# as14120_x31_fpga_power_conf.net
KiCad netlist of a schematic drawn in Altium Designer
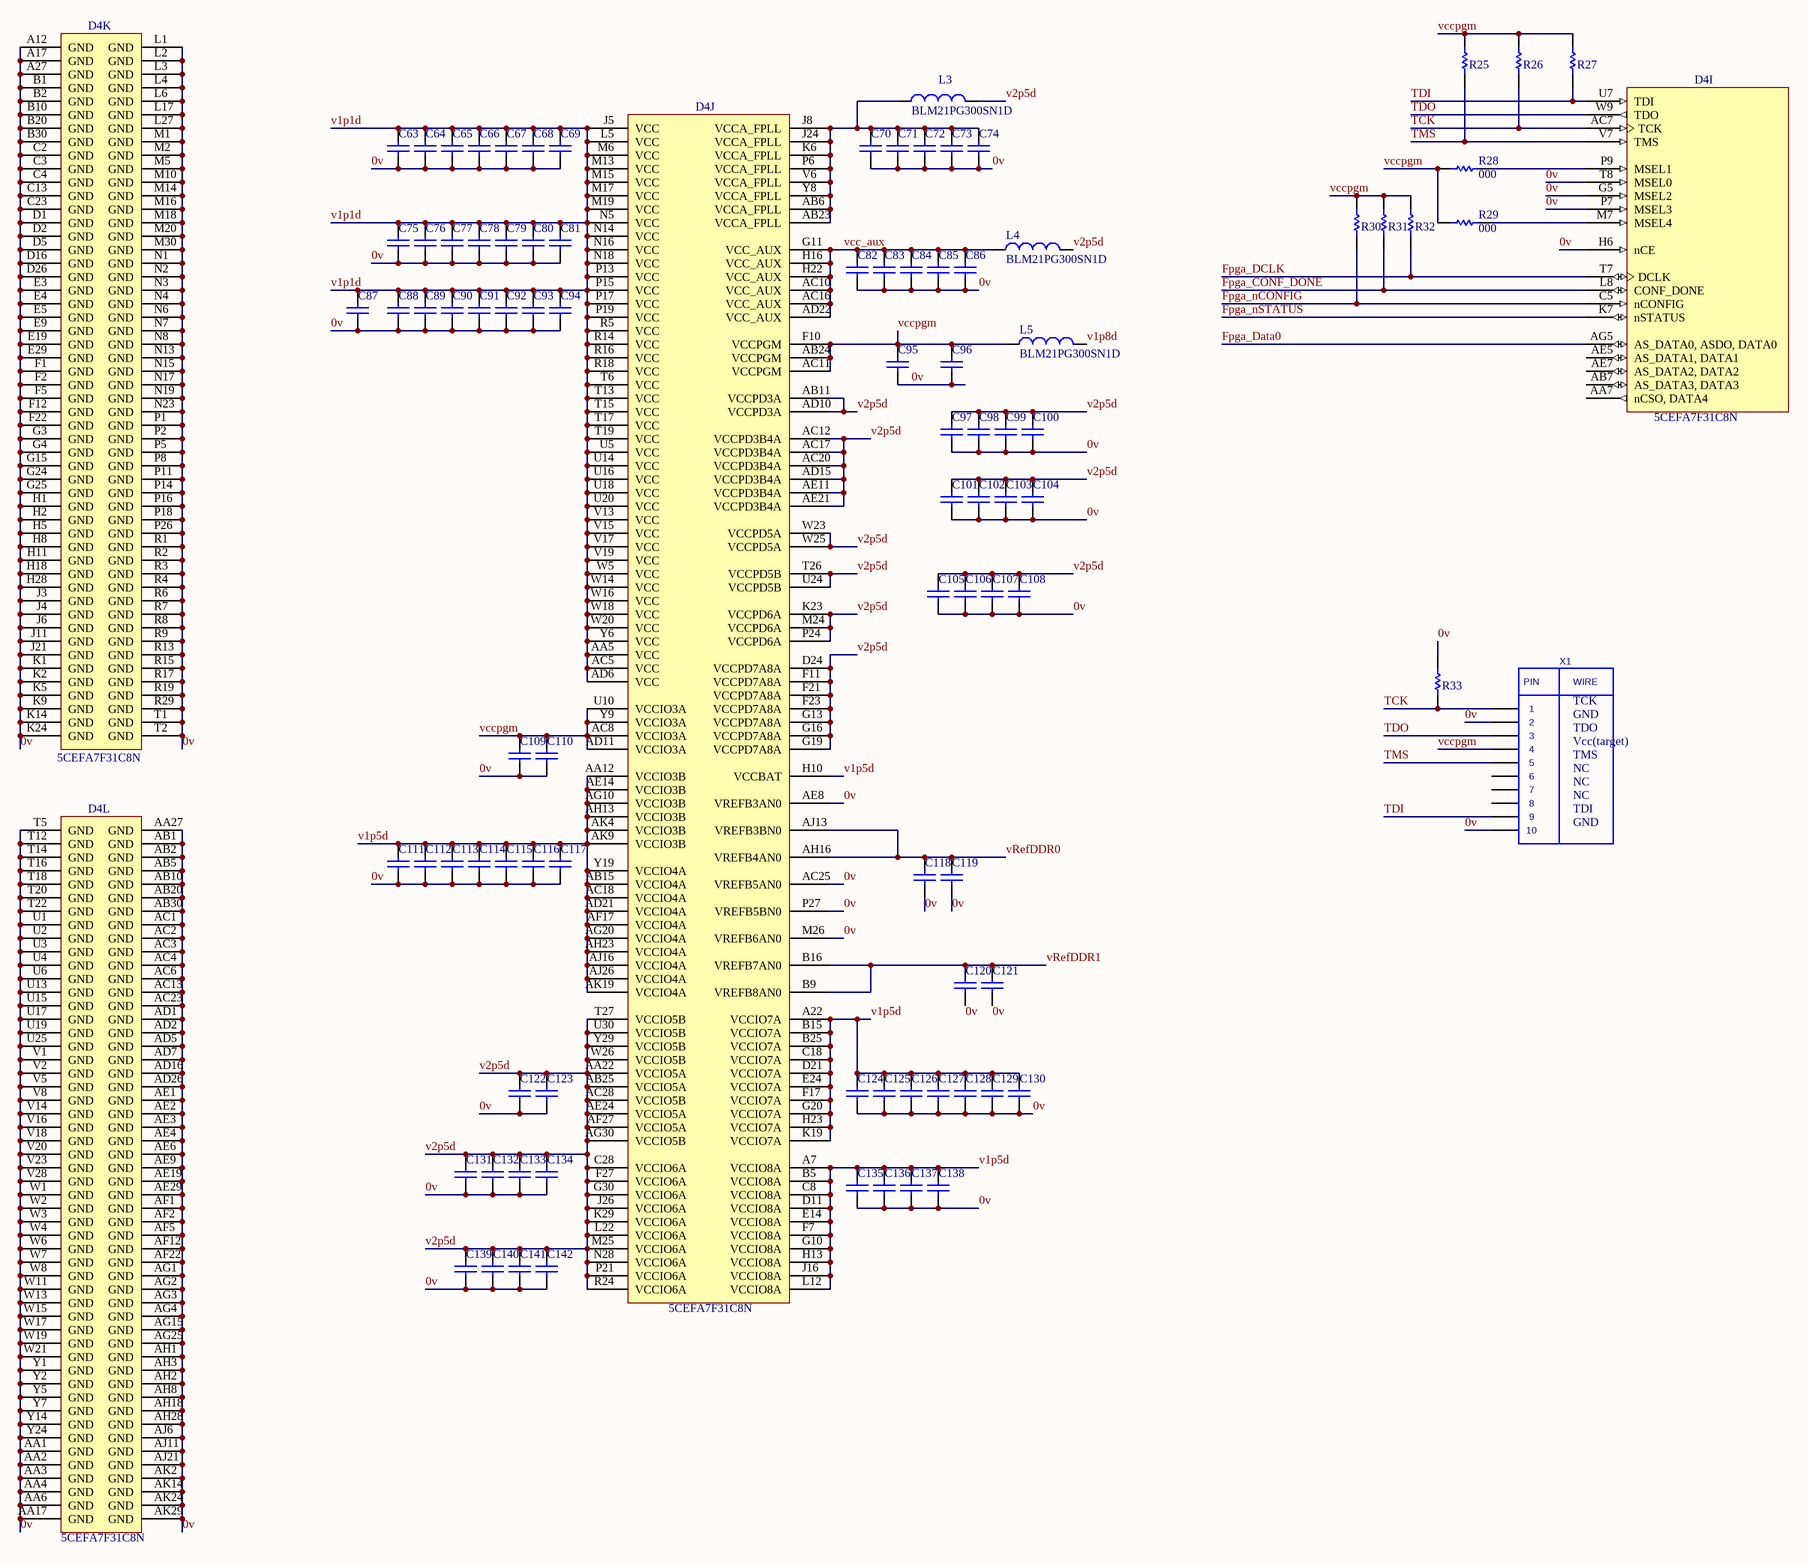
[diagram p0: as14120_x31_fpga_power_conf.SchDoc]

(export (version "E")
  (design (tool "Eeschema 10.0.6"))
  (components
    (comp (ref "C63")
      (value "CAP 1uF 10V 0402(1005)")
      (footprint "CAPC0402(1005)60_M")
      (description "CAP 1uF 10V ±20% 0402 (1005 Metric) Thickness 0.6mm SMD")
      (fields (field (name "TOLERANCE") "±20%"))
      (libsource (lib "as14120") (part "CAP_0402"))
    )
    (comp (ref "C64")
      (value "CAP 1uF 10V 0402(1005)")
      (footprint "CAPC0402(1005)60_M")
      (description "CAP 1uF 10V ±20% 0402 (1005 Metric) Thickness 0.6mm SMD")
      (fields (field (name "TOLERANCE") "±20%"))
      (libsource (lib "as14120") (part "CAP_0402"))
    )
    (comp (ref "C65")
      (value "CAP 1uF 10V 0402(1005)")
      (footprint "CAPC0402(1005)60_M")
      (description "CAP 1uF 10V ±20% 0402 (1005 Metric) Thickness 0.6mm SMD")
      (fields (field (name "TOLERANCE") "±20%"))
      (libsource (lib "as14120") (part "CAP_0402"))
    )
    (comp (ref "C66")
      (value "CAP 1uF 10V 0402(1005)")
      (footprint "CAPC0402(1005)60_M")
      (description "CAP 1uF 10V ±20% 0402 (1005 Metric) Thickness 0.6mm SMD")
      (fields (field (name "TOLERANCE") "±20%"))
      (libsource (lib "as14120") (part "CAP_0402"))
    )
    (comp (ref "C67")
      (value "CAP 1uF 10V 0402(1005)")
      (footprint "CAPC0402(1005)60_M")
      (description "CAP 1uF 10V ±20% 0402 (1005 Metric) Thickness 0.6mm SMD")
      (fields (field (name "TOLERANCE") "±20%"))
      (libsource (lib "as14120") (part "CAP_0402"))
    )
    (comp (ref "C68")
      (value "CAP 1uF 10V 0402(1005)")
      (footprint "CAPC0402(1005)60_M")
      (description "CAP 1uF 10V ±20% 0402 (1005 Metric) Thickness 0.6mm SMD")
      (fields (field (name "TOLERANCE") "±20%"))
      (libsource (lib "as14120") (part "CAP_0402"))
    )
    (comp (ref "C69")
      (value "CAP 1uF 10V 0402(1005)")
      (footprint "CAPC0402(1005)60_M")
      (description "CAP 1uF 10V ±20% 0402 (1005 Metric) Thickness 0.6mm SMD")
      (fields (field (name "TOLERANCE") "±20%"))
      (libsource (lib "as14120") (part "CAP_0402"))
    )
    (comp (ref "C70")
      (value "CAP 1uF 10V 0402(1005)")
      (footprint "CAPC0402(1005)60_M")
      (description "CAP 1uF 10V ±20% 0402 (1005 Metric) Thickness 0.6mm SMD")
      (fields (field (name "TOLERANCE") "±20%"))
      (libsource (lib "as14120") (part "CAP_0402"))
    )
    (comp (ref "C71")
      (value "CAP 1uF 10V 0402(1005)")
      (footprint "CAPC0402(1005)60_M")
      (description "CAP 1uF 10V ±20% 0402 (1005 Metric) Thickness 0.6mm SMD")
      (fields (field (name "TOLERANCE") "±20%"))
      (libsource (lib "as14120") (part "CAP_0402"))
    )
    (comp (ref "C72")
      (value "CAP 1uF 10V 0402(1005)")
      (footprint "CAPC0402(1005)60_M")
      (description "CAP 1uF 10V ±20% 0402 (1005 Metric) Thickness 0.6mm SMD")
      (fields (field (name "TOLERANCE") "±20%"))
      (libsource (lib "as14120") (part "CAP_0402"))
    )
    (comp (ref "C73")
      (value "CAP 1uF 10V 0402(1005)")
      (footprint "CAPC0402(1005)60_M")
      (description "CAP 1uF 10V ±20% 0402 (1005 Metric) Thickness 0.6mm SMD")
      (fields (field (name "TOLERANCE") "±20%"))
      (libsource (lib "as14120") (part "CAP_0402"))
    )
    (comp (ref "C74")
      (value "CAP 1uF 10V 0402(1005)")
      (footprint "CAPC0402(1005)60_M")
      (description "CAP 1uF 10V ±20% 0402 (1005 Metric) Thickness 0.6mm SMD")
      (fields (field (name "TOLERANCE") "±20%"))
      (libsource (lib "as14120") (part "CAP_0402"))
    )
    (comp (ref "C75")
      (value "CAP 1uF 10V 0402(1005)")
      (footprint "CAPC0402(1005)60_M")
      (description "CAP 1uF 10V ±20% 0402 (1005 Metric) Thickness 0.6mm SMD")
      (fields (field (name "TOLERANCE") "±20%"))
      (libsource (lib "as14120") (part "CAP_0402"))
    )
    (comp (ref "C76")
      (value "CAP 1uF 10V 0402(1005)")
      (footprint "CAPC0402(1005)60_M")
      (description "CAP 1uF 10V ±20% 0402 (1005 Metric) Thickness 0.6mm SMD")
      (fields (field (name "TOLERANCE") "±20%"))
      (libsource (lib "as14120") (part "CAP_0402"))
    )
    (comp (ref "C77")
      (value "CAP 1uF 10V 0402(1005)")
      (footprint "CAPC0402(1005)60_M")
      (description "CAP 1uF 10V ±20% 0402 (1005 Metric) Thickness 0.6mm SMD")
      (fields (field (name "TOLERANCE") "±20%"))
      (libsource (lib "as14120") (part "CAP_0402"))
    )
    (comp (ref "C78")
      (value "CAP 1uF 10V 0402(1005)")
      (footprint "CAPC0402(1005)60_M")
      (description "CAP 1uF 10V ±20% 0402 (1005 Metric) Thickness 0.6mm SMD")
      (fields (field (name "TOLERANCE") "±20%"))
      (libsource (lib "as14120") (part "CAP_0402"))
    )
    (comp (ref "C79")
      (value "CAP 1uF 10V 0402(1005)")
      (footprint "CAPC0402(1005)60_M")
      (description "CAP 1uF 10V ±20% 0402 (1005 Metric) Thickness 0.6mm SMD")
      (fields (field (name "TOLERANCE") "±20%"))
      (libsource (lib "as14120") (part "CAP_0402"))
    )
    (comp (ref "C80")
      (value "CAP 1uF 10V 0402(1005)")
      (footprint "CAPC0402(1005)60_M")
      (description "CAP 1uF 10V ±20% 0402 (1005 Metric) Thickness 0.6mm SMD")
      (fields (field (name "TOLERANCE") "±20%"))
      (libsource (lib "as14120") (part "CAP_0402"))
    )
    (comp (ref "C81")
      (value "CAP 1uF 10V 0402(1005)")
      (footprint "CAPC0402(1005)60_M")
      (description "CAP 1uF 10V ±20% 0402 (1005 Metric) Thickness 0.6mm SMD")
      (fields (field (name "TOLERANCE") "±20%"))
      (libsource (lib "as14120") (part "CAP_0402"))
    )
    (comp (ref "C82")
      (value "CAP 1uF 10V 0402(1005)")
      (footprint "CAPC0402(1005)60_M")
      (description "CAP 1uF 10V ±20% 0402 (1005 Metric) Thickness 0.6mm SMD")
      (fields (field (name "TOLERANCE") "±20%"))
      (libsource (lib "as14120") (part "CAP_0402"))
    )
    (comp (ref "C83")
      (value "CAP 1uF 10V 0402(1005)")
      (footprint "CAPC0402(1005)60_M")
      (description "CAP 1uF 10V ±20% 0402 (1005 Metric) Thickness 0.6mm SMD")
      (fields (field (name "TOLERANCE") "±20%"))
      (libsource (lib "as14120") (part "CAP_0402"))
    )
    (comp (ref "C84")
      (value "CAP 1uF 10V 0402(1005)")
      (footprint "CAPC0402(1005)60_M")
      (description "CAP 1uF 10V ±20% 0402 (1005 Metric) Thickness 0.6mm SMD")
      (fields (field (name "TOLERANCE") "±20%"))
      (libsource (lib "as14120") (part "CAP_0402"))
    )
    (comp (ref "C85")
      (value "CAP 1uF 10V 0402(1005)")
      (footprint "CAPC0402(1005)60_M")
      (description "CAP 1uF 10V ±20% 0402 (1005 Metric) Thickness 0.6mm SMD")
      (fields (field (name "TOLERANCE") "±20%"))
      (libsource (lib "as14120") (part "CAP_0402"))
    )
    (comp (ref "C86")
      (value "CAP 1uF 10V 0402(1005)")
      (footprint "CAPC0402(1005)60_M")
      (description "CAP 1uF 10V ±20% 0402 (1005 Metric) Thickness 0.6mm SMD")
      (fields (field (name "TOLERANCE") "±20%"))
      (libsource (lib "as14120") (part "CAP_0402"))
    )
    (comp (ref "C87")
      (value "CAP 1uF 10V 0402(1005)")
      (footprint "CAPC0402(1005)60_M")
      (description "CAP 1uF 10V ±20% 0402 (1005 Metric) Thickness 0.6mm SMD")
      (fields (field (name "TOLERANCE") "±20%"))
      (libsource (lib "as14120") (part "CAP_0402"))
    )
    (comp (ref "C88")
      (value "CAP 1uF 10V 0402(1005)")
      (footprint "CAPC0402(1005)60_M")
      (description "CAP 1uF 10V ±20% 0402 (1005 Metric) Thickness 0.6mm SMD")
      (fields (field (name "TOLERANCE") "±20%"))
      (libsource (lib "as14120") (part "CAP_0402"))
    )
    (comp (ref "C89")
      (value "CAP 1uF 10V 0402(1005)")
      (footprint "CAPC0402(1005)60_M")
      (description "CAP 1uF 10V ±20% 0402 (1005 Metric) Thickness 0.6mm SMD")
      (fields (field (name "TOLERANCE") "±20%"))
      (libsource (lib "as14120") (part "CAP_0402"))
    )
    (comp (ref "C90")
      (value "CAP 1uF 10V 0402(1005)")
      (footprint "CAPC0402(1005)60_M")
      (description "CAP 1uF 10V ±20% 0402 (1005 Metric) Thickness 0.6mm SMD")
      (fields (field (name "TOLERANCE") "±20%"))
      (libsource (lib "as14120") (part "CAP_0402"))
    )
    (comp (ref "C91")
      (value "CAP 1uF 10V 0402(1005)")
      (footprint "CAPC0402(1005)60_M")
      (description "CAP 1uF 10V ±20% 0402 (1005 Metric) Thickness 0.6mm SMD")
      (fields (field (name "TOLERANCE") "±20%"))
      (libsource (lib "as14120") (part "CAP_0402"))
    )
    (comp (ref "C92")
      (value "CAP 1uF 10V 0402(1005)")
      (footprint "CAPC0402(1005)60_M")
      (description "CAP 1uF 10V ±20% 0402 (1005 Metric) Thickness 0.6mm SMD")
      (fields (field (name "TOLERANCE") "±20%"))
      (libsource (lib "as14120") (part "CAP_0402"))
    )
    (comp (ref "C93")
      (value "CAP 1uF 10V 0402(1005)")
      (footprint "CAPC0402(1005)60_M")
      (description "CAP 1uF 10V ±20% 0402 (1005 Metric) Thickness 0.6mm SMD")
      (fields (field (name "TOLERANCE") "±20%"))
      (libsource (lib "as14120") (part "CAP_0402"))
    )
    (comp (ref "C94")
      (value "CAP 1uF 10V 0402(1005)")
      (footprint "CAPC0402(1005)60_M")
      (description "CAP 1uF 10V ±20% 0402 (1005 Metric) Thickness 0.6mm SMD")
      (fields (field (name "TOLERANCE") "±20%"))
      (libsource (lib "as14120") (part "CAP_0402"))
    )
    (comp (ref "C95")
      (value "CAP 1uF 10V 0402(1005)")
      (footprint "CAPC0402(1005)60_M")
      (description "CAP 1uF 10V ±20% 0402 (1005 Metric) Thickness 0.6mm SMD")
      (fields (field (name "TOLERANCE") "±20%"))
      (libsource (lib "as14120") (part "CAP_0402"))
    )
    (comp (ref "C96")
      (value "CAP 1uF 10V 0402(1005)")
      (footprint "CAPC0402(1005)60_M")
      (description "CAP 1uF 10V ±20% 0402 (1005 Metric) Thickness 0.6mm SMD")
      (fields (field (name "TOLERANCE") "±20%"))
      (libsource (lib "as14120") (part "CAP_0402"))
    )
    (comp (ref "C97")
      (value "CAP 1uF 10V 0402(1005)")
      (footprint "CAPC0402(1005)60_M")
      (description "CAP 1uF 10V ±20% 0402 (1005 Metric) Thickness 0.6mm SMD")
      (fields (field (name "TOLERANCE") "±20%"))
      (libsource (lib "as14120") (part "CAP_0402"))
    )
    (comp (ref "C98")
      (value "CAP 1uF 10V 0402(1005)")
      (footprint "CAPC0402(1005)60_M")
      (description "CAP 1uF 10V ±20% 0402 (1005 Metric) Thickness 0.6mm SMD")
      (fields (field (name "TOLERANCE") "±20%"))
      (libsource (lib "as14120") (part "CAP_0402"))
    )
    (comp (ref "C99")
      (value "CAP 1uF 10V 0402(1005)")
      (footprint "CAPC0402(1005)60_M")
      (description "CAP 1uF 10V ±20% 0402 (1005 Metric) Thickness 0.6mm SMD")
      (fields (field (name "TOLERANCE") "±20%"))
      (libsource (lib "as14120") (part "CAP_0402"))
    )
    (comp (ref "C100")
      (value "CAP 1uF 10V 0402(1005)")
      (footprint "CAPC0402(1005)60_M")
      (description "CAP 1uF 10V ±20% 0402 (1005 Metric) Thickness 0.6mm SMD")
      (fields (field (name "TOLERANCE") "±20%"))
      (libsource (lib "as14120") (part "CAP_0402"))
    )
    (comp (ref "C101")
      (value "CAP 1uF 10V 0402(1005)")
      (footprint "CAPC0402(1005)60_M")
      (description "CAP 1uF 10V ±20% 0402 (1005 Metric) Thickness 0.6mm SMD")
      (fields (field (name "TOLERANCE") "±20%"))
      (libsource (lib "as14120") (part "CAP_0402"))
    )
    (comp (ref "C102")
      (value "CAP 1uF 10V 0402(1005)")
      (footprint "CAPC0402(1005)60_M")
      (description "CAP 1uF 10V ±20% 0402 (1005 Metric) Thickness 0.6mm SMD")
      (fields (field (name "TOLERANCE") "±20%"))
      (libsource (lib "as14120") (part "CAP_0402"))
    )
    (comp (ref "C103")
      (value "CAP 1uF 10V 0402(1005)")
      (footprint "CAPC0402(1005)60_M")
      (description "CAP 1uF 10V ±20% 0402 (1005 Metric) Thickness 0.6mm SMD")
      (fields (field (name "TOLERANCE") "±20%"))
      (libsource (lib "as14120") (part "CAP_0402"))
    )
    (comp (ref "C104")
      (value "CAP 1uF 10V 0402(1005)")
      (footprint "CAPC0402(1005)60_M")
      (description "CAP 1uF 10V ±20% 0402 (1005 Metric) Thickness 0.6mm SMD")
      (fields (field (name "TOLERANCE") "±20%"))
      (libsource (lib "as14120") (part "CAP_0402"))
    )
    (comp (ref "C105")
      (value "CAP 1uF 10V 0402(1005)")
      (footprint "CAPC0402(1005)60_M")
      (description "CAP 1uF 10V ±20% 0402 (1005 Metric) Thickness 0.6mm SMD")
      (fields (field (name "TOLERANCE") "±20%"))
      (libsource (lib "as14120") (part "CAP_0402"))
    )
    (comp (ref "C106")
      (value "CAP 1uF 10V 0402(1005)")
      (footprint "CAPC0402(1005)60_M")
      (description "CAP 1uF 10V ±20% 0402 (1005 Metric) Thickness 0.6mm SMD")
      (fields (field (name "TOLERANCE") "±20%"))
      (libsource (lib "as14120") (part "CAP_0402"))
    )
    (comp (ref "C107")
      (value "CAP 1uF 10V 0402(1005)")
      (footprint "CAPC0402(1005)60_M")
      (description "CAP 1uF 10V ±20% 0402 (1005 Metric) Thickness 0.6mm SMD")
      (fields (field (name "TOLERANCE") "±20%"))
      (libsource (lib "as14120") (part "CAP_0402"))
    )
    (comp (ref "C108")
      (value "CAP 1uF 10V 0402(1005)")
      (footprint "CAPC0402(1005)60_M")
      (description "CAP 1uF 10V ±20% 0402 (1005 Metric) Thickness 0.6mm SMD")
      (fields (field (name "TOLERANCE") "±20%"))
      (libsource (lib "as14120") (part "CAP_0402"))
    )
    (comp (ref "C109")
      (value "CAP 1uF 10V 0402(1005)")
      (footprint "CAPC0402(1005)60_M")
      (description "CAP 1uF 10V ±20% 0402 (1005 Metric) Thickness 0.6mm SMD")
      (fields (field (name "TOLERANCE") "±20%"))
      (libsource (lib "as14120") (part "CAP_0402"))
    )
    (comp (ref "C110")
      (value "CAP 1uF 10V 0402(1005)")
      (footprint "CAPC0402(1005)60_M")
      (description "CAP 1uF 10V ±20% 0402 (1005 Metric) Thickness 0.6mm SMD")
      (fields (field (name "TOLERANCE") "±20%"))
      (libsource (lib "as14120") (part "CAP_0402"))
    )
    (comp (ref "C111")
      (value "CAP 1uF 10V 0402(1005)")
      (footprint "CAPC0402(1005)60_M")
      (description "CAP 1uF 10V ±20% 0402 (1005 Metric) Thickness 0.6mm SMD")
      (fields (field (name "TOLERANCE") "±20%"))
      (libsource (lib "as14120") (part "CAP_0402"))
    )
    (comp (ref "C112")
      (value "CAP 1uF 10V 0402(1005)")
      (footprint "CAPC0402(1005)60_M")
      (description "CAP 1uF 10V ±20% 0402 (1005 Metric) Thickness 0.6mm SMD")
      (fields (field (name "TOLERANCE") "±20%"))
      (libsource (lib "as14120") (part "CAP_0402"))
    )
    (comp (ref "C113")
      (value "CAP 1uF 10V 0402(1005)")
      (footprint "CAPC0402(1005)60_M")
      (description "CAP 1uF 10V ±20% 0402 (1005 Metric) Thickness 0.6mm SMD")
      (fields (field (name "TOLERANCE") "±20%"))
      (libsource (lib "as14120") (part "CAP_0402"))
    )
    (comp (ref "C114")
      (value "CAP 1uF 10V 0402(1005)")
      (footprint "CAPC0402(1005)60_M")
      (description "CAP 1uF 10V ±20% 0402 (1005 Metric) Thickness 0.6mm SMD")
      (fields (field (name "TOLERANCE") "±20%"))
      (libsource (lib "as14120") (part "CAP_0402"))
    )
    (comp (ref "C115")
      (value "CAP 1uF 10V 0402(1005)")
      (footprint "CAPC0402(1005)60_M")
      (description "CAP 1uF 10V ±20% 0402 (1005 Metric) Thickness 0.6mm SMD")
      (fields (field (name "TOLERANCE") "±20%"))
      (libsource (lib "as14120") (part "CAP_0402"))
    )
    (comp (ref "C116")
      (value "CAP 1uF 10V 0402(1005)")
      (footprint "CAPC0402(1005)60_M")
      (description "CAP 1uF 10V ±20% 0402 (1005 Metric) Thickness 0.6mm SMD")
      (fields (field (name "TOLERANCE") "±20%"))
      (libsource (lib "as14120") (part "CAP_0402"))
    )
    (comp (ref "C117")
      (value "CAP 1uF 10V 0402(1005)")
      (footprint "CAPC0402(1005)60_M")
      (description "CAP 1uF 10V ±20% 0402 (1005 Metric) Thickness 0.6mm SMD")
      (fields (field (name "TOLERANCE") "±20%"))
      (libsource (lib "as14120") (part "CAP_0402"))
    )
    (comp (ref "C118")
      (value "CAP 1uF 10V 0402(1005)")
      (footprint "CAPC0402(1005)60_M")
      (description "CAP 1uF 10V ±20% 0402 (1005 Metric) Thickness 0.6mm SMD")
      (fields (field (name "TOLERANCE") "±20%"))
      (libsource (lib "as14120") (part "CAP_0402"))
    )
    (comp (ref "C119")
      (value "CAP 1uF 10V 0402(1005)")
      (footprint "CAPC0402(1005)60_M")
      (description "CAP 1uF 10V ±20% 0402 (1005 Metric) Thickness 0.6mm SMD")
      (fields (field (name "TOLERANCE") "±20%"))
      (libsource (lib "as14120") (part "CAP_0402"))
    )
    (comp (ref "C120")
      (value "CAP 1uF 10V 0402(1005)")
      (footprint "CAPC0402(1005)60_M")
      (description "CAP 1uF 10V ±20% 0402 (1005 Metric) Thickness 0.6mm SMD")
      (fields (field (name "TOLERANCE") "±20%"))
      (libsource (lib "as14120") (part "CAP_0402"))
    )
    (comp (ref "C121")
      (value "CAP 1uF 10V 0402(1005)")
      (footprint "CAPC0402(1005)60_M")
      (description "CAP 1uF 10V ±20% 0402 (1005 Metric) Thickness 0.6mm SMD")
      (fields (field (name "TOLERANCE") "±20%"))
      (libsource (lib "as14120") (part "CAP_0402"))
    )
    (comp (ref "C122")
      (value "CAP 1uF 10V 0402(1005)")
      (footprint "CAPC0402(1005)60_M")
      (description "CAP 1uF 10V ±20% 0402 (1005 Metric) Thickness 0.6mm SMD")
      (fields (field (name "TOLERANCE") "±20%"))
      (libsource (lib "as14120") (part "CAP_0402"))
    )
    (comp (ref "C123")
      (value "CAP 1uF 10V 0402(1005)")
      (footprint "CAPC0402(1005)60_M")
      (description "CAP 1uF 10V ±20% 0402 (1005 Metric) Thickness 0.6mm SMD")
      (fields (field (name "TOLERANCE") "±20%"))
      (libsource (lib "as14120") (part "CAP_0402"))
    )
    (comp (ref "C124")
      (value "CAP 1uF 10V 0402(1005)")
      (footprint "CAPC0402(1005)60_M")
      (description "CAP 1uF 10V ±20% 0402 (1005 Metric) Thickness 0.6mm SMD")
      (fields (field (name "TOLERANCE") "±20%"))
      (libsource (lib "as14120") (part "CAP_0402"))
    )
    (comp (ref "C125")
      (value "CAP 1uF 10V 0402(1005)")
      (footprint "CAPC0402(1005)60_M")
      (description "CAP 1uF 10V ±20% 0402 (1005 Metric) Thickness 0.6mm SMD")
      (fields (field (name "TOLERANCE") "±20%"))
      (libsource (lib "as14120") (part "CAP_0402"))
    )
    (comp (ref "C126")
      (value "CAP 1uF 10V 0402(1005)")
      (footprint "CAPC0402(1005)60_M")
      (description "CAP 1uF 10V ±20% 0402 (1005 Metric) Thickness 0.6mm SMD")
      (fields (field (name "TOLERANCE") "±20%"))
      (libsource (lib "as14120") (part "CAP_0402"))
    )
    (comp (ref "C127")
      (value "CAP 1uF 10V 0402(1005)")
      (footprint "CAPC0402(1005)60_M")
      (description "CAP 1uF 10V ±20% 0402 (1005 Metric) Thickness 0.6mm SMD")
      (fields (field (name "TOLERANCE") "±20%"))
      (libsource (lib "as14120") (part "CAP_0402"))
    )
    (comp (ref "C128")
      (value "CAP 1uF 10V 0402(1005)")
      (footprint "CAPC0402(1005)60_M")
      (description "CAP 1uF 10V ±20% 0402 (1005 Metric) Thickness 0.6mm SMD")
      (fields (field (name "TOLERANCE") "±20%"))
      (libsource (lib "as14120") (part "CAP_0402"))
    )
    (comp (ref "C129")
      (value "CAP 1uF 10V 0402(1005)")
      (footprint "CAPC0402(1005)60_M")
      (description "CAP 1uF 10V ±20% 0402 (1005 Metric) Thickness 0.6mm SMD")
      (fields (field (name "TOLERANCE") "±20%"))
      (libsource (lib "as14120") (part "CAP_0402"))
    )
    (comp (ref "C130")
      (value "CAP 1uF 10V 0402(1005)")
      (footprint "CAPC0402(1005)60_M")
      (description "CAP 1uF 10V ±20% 0402 (1005 Metric) Thickness 0.6mm SMD")
      (fields (field (name "TOLERANCE") "±20%"))
      (libsource (lib "as14120") (part "CAP_0402"))
    )
    (comp (ref "C131")
      (value "CAP 1uF 10V 0402(1005)")
      (footprint "CAPC0402(1005)60_M")
      (description "CAP 1uF 10V ±20% 0402 (1005 Metric) Thickness 0.6mm SMD")
      (fields (field (name "TOLERANCE") "±20%"))
      (libsource (lib "as14120") (part "CAP_0402"))
    )
    (comp (ref "C132")
      (value "CAP 1uF 10V 0402(1005)")
      (footprint "CAPC0402(1005)60_M")
      (description "CAP 1uF 10V ±20% 0402 (1005 Metric) Thickness 0.6mm SMD")
      (fields (field (name "TOLERANCE") "±20%"))
      (libsource (lib "as14120") (part "CAP_0402"))
    )
    (comp (ref "C133")
      (value "CAP 1uF 10V 0402(1005)")
      (footprint "CAPC0402(1005)60_M")
      (description "CAP 1uF 10V ±20% 0402 (1005 Metric) Thickness 0.6mm SMD")
      (fields (field (name "TOLERANCE") "±20%"))
      (libsource (lib "as14120") (part "CAP_0402"))
    )
    (comp (ref "C134")
      (value "CAP 1uF 10V 0402(1005)")
      (footprint "CAPC0402(1005)60_M")
      (description "CAP 1uF 10V ±20% 0402 (1005 Metric) Thickness 0.6mm SMD")
      (fields (field (name "TOLERANCE") "±20%"))
      (libsource (lib "as14120") (part "CAP_0402"))
    )
    (comp (ref "C135")
      (value "CAP 1uF 10V 0402(1005)")
      (footprint "CAPC0402(1005)60_M")
      (description "CAP 1uF 10V ±20% 0402 (1005 Metric) Thickness 0.6mm SMD")
      (fields (field (name "TOLERANCE") "±20%"))
      (libsource (lib "as14120") (part "CAP_0402"))
    )
    (comp (ref "C136")
      (value "CAP 1uF 10V 0402(1005)")
      (footprint "CAPC0402(1005)60_M")
      (description "CAP 1uF 10V ±20% 0402 (1005 Metric) Thickness 0.6mm SMD")
      (fields (field (name "TOLERANCE") "±20%"))
      (libsource (lib "as14120") (part "CAP_0402"))
    )
    (comp (ref "C137")
      (value "CAP 1uF 10V 0402(1005)")
      (footprint "CAPC0402(1005)60_M")
      (description "CAP 1uF 10V ±20% 0402 (1005 Metric) Thickness 0.6mm SMD")
      (fields (field (name "TOLERANCE") "±20%"))
      (libsource (lib "as14120") (part "CAP_0402"))
    )
    (comp (ref "C138")
      (value "CAP 1uF 10V 0402(1005)")
      (footprint "CAPC0402(1005)60_M")
      (description "CAP 1uF 10V ±20% 0402 (1005 Metric) Thickness 0.6mm SMD")
      (fields (field (name "TOLERANCE") "±20%"))
      (libsource (lib "as14120") (part "CAP_0402"))
    )
    (comp (ref "C139")
      (value "CAP 1uF 10V 0402(1005)")
      (footprint "CAPC0402(1005)60_M")
      (description "CAP 1uF 10V ±20% 0402 (1005 Metric) Thickness 0.6mm SMD")
      (fields (field (name "TOLERANCE") "±20%"))
      (libsource (lib "as14120") (part "CAP_0402"))
    )
    (comp (ref "C140")
      (value "CAP 1uF 10V 0402(1005)")
      (footprint "CAPC0402(1005)60_M")
      (description "CAP 1uF 10V ±20% 0402 (1005 Metric) Thickness 0.6mm SMD")
      (fields (field (name "TOLERANCE") "±20%"))
      (libsource (lib "as14120") (part "CAP_0402"))
    )
    (comp (ref "C141")
      (value "CAP 1uF 10V 0402(1005)")
      (footprint "CAPC0402(1005)60_M")
      (description "CAP 1uF 10V ±20% 0402 (1005 Metric) Thickness 0.6mm SMD")
      (fields (field (name "TOLERANCE") "±20%"))
      (libsource (lib "as14120") (part "CAP_0402"))
    )
    (comp (ref "C142")
      (value "CAP 1uF 10V 0402(1005)")
      (footprint "CAPC0402(1005)60_M")
      (description "CAP 1uF 10V ±20% 0402 (1005 Metric) Thickness 0.6mm SMD")
      (fields (field (name "TOLERANCE") "±20%"))
      (libsource (lib "as14120") (part "CAP_0402"))
    )
    (comp (ref "D4")
      (value "5CEFA7F31C8N")
      (footprint "ALTR-896-FBGA-2000A")
      (fields (field (name "MANUFACTURER") "Altera"))
      (libsource (lib "Altera Cyclone V E") (part "5CEFA7F31C8N"))
    )
    (comp (ref "L3")
      (value "BLM21PG300SN1D")
      (footprint "CAPC0805(2012)100_N")
      (libsource (lib "as14120") (part "Ferrite_beat"))
    )
    (comp (ref "L4")
      (value "BLM21PG300SN1D")
      (footprint "CAPC0805(2012)100_N")
      (libsource (lib "as14120") (part "Ferrite_beat"))
    )
    (comp (ref "L5")
      (value "BLM21PG300SN1D")
      (footprint "CAPC0805(2012)100_N")
      (libsource (lib "as14120") (part "Ferrite_beat"))
    )
    (comp (ref "R25")
      (value "1K 5% 0603(1608)")
      (footprint "RESC0603(1608)_L")
      (description "1K 0.1W 5% 0603 (1608 Metric)  SMD")
      (fields (field (name "TOLERANCE") "5 %") (field (name "POWER") "0.1 W"))
      (libsource (lib "as14120") (part "RES_0603"))
    )
    (comp (ref "R26")
      (value "1K 5% 0603(1608)")
      (footprint "RESC0603(1608)_L")
      (description "1K 0.1W 5% 0603 (1608 Metric)  SMD")
      (fields (field (name "TOLERANCE") "5 %") (field (name "POWER") "0.1 W"))
      (libsource (lib "as14120") (part "RES_0603"))
    )
    (comp (ref "R27")
      (value "1K 5% 0603(1608)")
      (footprint "RESC0603(1608)_L")
      (description "1K 0.1W 5% 0603 (1608 Metric)  SMD")
      (fields (field (name "TOLERANCE") "5 %") (field (name "POWER") "0.1 W"))
      (libsource (lib "as14120") (part "RES_0603"))
    )
    (comp (ref "R28")
      (value "000")
      (footprint "RESC0603(1608)_L")
      (description "1K 0.1W 5% 0603 (1608 Metric)  SMD")
      (fields (field (name "TOLERANCE") "5 %") (field (name "POWER") "0.1 W"))
      (libsource (lib "as14120") (part "RES_0603"))
    )
    (comp (ref "R29")
      (value "000")
      (footprint "RESC0603(1608)_L")
      (description "1K 0.1W 5% 0603 (1608 Metric)  SMD")
      (fields (field (name "TOLERANCE") "5 %") (field (name "POWER") "0.1 W"))
      (libsource (lib "as14120") (part "RES_0603"))
    )
    (comp (ref "R30")
      (value "1K 5% 0603(1608)")
      (footprint "RESC0603(1608)_L")
      (description "1K 0.1W 5% 0603 (1608 Metric)  SMD")
      (fields (field (name "TOLERANCE") "5 %") (field (name "POWER") "0.1 W"))
      (libsource (lib "as14120") (part "RES_0603"))
    )
    (comp (ref "R31")
      (value "1K 5% 0603(1608)")
      (footprint "RESC0603(1608)_L")
      (description "1K 0.1W 5% 0603 (1608 Metric)  SMD")
      (fields (field (name "TOLERANCE") "5 %") (field (name "POWER") "0.1 W"))
      (libsource (lib "as14120") (part "RES_0603"))
    )
    (comp (ref "R32")
      (value "1K 5% 0603(1608)")
      (footprint "RESC0603(1608)_L")
      (description "1K 0.1W 5% 0603 (1608 Metric)  SMD")
      (fields (field (name "TOLERANCE") "5 %") (field (name "POWER") "0.1 W"))
      (libsource (lib "as14120") (part "RES_0603"))
    )
    (comp (ref "R33")
      (value "1K 5% 0603(1608)")
      (footprint "RESC0603(1608)_L")
      (description "1K 0.1W 5% 0603 (1608 Metric)  SMD")
      (fields (field (name "TOLERANCE") "5 %") (field (name "POWER") "0.1 W"))
      (libsource (lib "as14120") (part "RES_0603"))
    )
    (comp (ref "X1") (value "IDC10") (footprint "IDC10M") (libsource (lib "alexsb") (part "IDC10")))
  )
  (nets
    (net (code "1") (name "/0v") (class "Default")
      (node (ref "C100") (pin "1") (pinfunction "1_1") (pintype "passive"))
      (node (ref "C101") (pin "1") (pinfunction "1_1") (pintype "passive"))
      (node (ref "C102") (pin "1") (pinfunction "1_1") (pintype "passive"))
      (node (ref "C103") (pin "1") (pinfunction "1_1") (pintype "passive"))
      (node (ref "C104") (pin "1") (pinfunction "1_1") (pintype "passive"))
      (node (ref "C105") (pin "1") (pinfunction "1_1") (pintype "passive"))
      (node (ref "C106") (pin "1") (pinfunction "1_1") (pintype "passive"))
      (node (ref "C107") (pin "1") (pinfunction "1_1") (pintype "passive"))
      (node (ref "C108") (pin "1") (pinfunction "1_1") (pintype "passive"))
      (node (ref "C109") (pin "1") (pinfunction "1_1") (pintype "passive"))
      (node (ref "C110") (pin "1") (pinfunction "1_1") (pintype "passive"))
      (node (ref "C111") (pin "1") (pinfunction "1_1") (pintype "passive"))
      (node (ref "C112") (pin "1") (pinfunction "1_1") (pintype "passive"))
      (node (ref "C113") (pin "1") (pinfunction "1_1") (pintype "passive"))
      (node (ref "C114") (pin "1") (pinfunction "1_1") (pintype "passive"))
      (node (ref "C115") (pin "1") (pinfunction "1_1") (pintype "passive"))
      (node (ref "C116") (pin "1") (pinfunction "1_1") (pintype "passive"))
      (node (ref "C117") (pin "1") (pinfunction "1_1") (pintype "passive"))
      (node (ref "C118") (pin "1") (pinfunction "1_1") (pintype "passive"))
      (node (ref "C119") (pin "1") (pinfunction "1_1") (pintype "passive"))
      (node (ref "C122") (pin "1") (pinfunction "1_1") (pintype "passive"))
      (node (ref "C123") (pin "1") (pinfunction "1_1") (pintype "passive"))
      (node (ref "C124") (pin "1") (pinfunction "1_1") (pintype "passive"))
      (node (ref "C125") (pin "1") (pinfunction "1_1") (pintype "passive"))
      (node (ref "C126") (pin "1") (pinfunction "1_1") (pintype "passive"))
      (node (ref "C127") (pin "1") (pinfunction "1_1") (pintype "passive"))
      (node (ref "C128") (pin "1") (pinfunction "1_1") (pintype "passive"))
      (node (ref "C129") (pin "1") (pinfunction "1_1") (pintype "passive"))
      (node (ref "C130") (pin "1") (pinfunction "1_1") (pintype "passive"))
      (node (ref "C131") (pin "1") (pinfunction "1_1") (pintype "passive"))
      (node (ref "C132") (pin "1") (pinfunction "1_1") (pintype "passive"))
      (node (ref "C133") (pin "1") (pinfunction "1_1") (pintype "passive"))
      (node (ref "C134") (pin "1") (pinfunction "1_1") (pintype "passive"))
      (node (ref "C135") (pin "1") (pinfunction "1_1") (pintype "passive"))
      (node (ref "C136") (pin "1") (pinfunction "1_1") (pintype "passive"))
      (node (ref "C137") (pin "1") (pinfunction "1_1") (pintype "passive"))
      (node (ref "C138") (pin "1") (pinfunction "1_1") (pintype "passive"))
      (node (ref "C139") (pin "1") (pinfunction "1_1") (pintype "passive"))
      (node (ref "C140") (pin "1") (pinfunction "1_1") (pintype "passive"))
      (node (ref "C141") (pin "1") (pinfunction "1_1") (pintype "passive"))
      (node (ref "C142") (pin "1") (pinfunction "1_1") (pintype "passive"))
      (node (ref "C63") (pin "1") (pinfunction "1_1") (pintype "passive"))
      (node (ref "C64") (pin "1") (pinfunction "1_1") (pintype "passive"))
      (node (ref "C65") (pin "1") (pinfunction "1_1") (pintype "passive"))
      (node (ref "C66") (pin "1") (pinfunction "1_1") (pintype "passive"))
      (node (ref "C67") (pin "1") (pinfunction "1_1") (pintype "passive"))
      (node (ref "C68") (pin "1") (pinfunction "1_1") (pintype "passive"))
      (node (ref "C69") (pin "1") (pinfunction "1_1") (pintype "passive"))
      (node (ref "C70") (pin "1") (pinfunction "1_1") (pintype "passive"))
      (node (ref "C71") (pin "1") (pinfunction "1_1") (pintype "passive"))
      (node (ref "C72") (pin "1") (pinfunction "1_1") (pintype "passive"))
      (node (ref "C73") (pin "1") (pinfunction "1_1") (pintype "passive"))
      (node (ref "C74") (pin "1") (pinfunction "1_1") (pintype "passive"))
      (node (ref "C75") (pin "1") (pinfunction "1_1") (pintype "passive"))
      (node (ref "C76") (pin "1") (pinfunction "1_1") (pintype "passive"))
      (node (ref "C77") (pin "1") (pinfunction "1_1") (pintype "passive"))
      (node (ref "C78") (pin "1") (pinfunction "1_1") (pintype "passive"))
      (node (ref "C79") (pin "1") (pinfunction "1_1") (pintype "passive"))
      (node (ref "C80") (pin "1") (pinfunction "1_1") (pintype "passive"))
      (node (ref "C81") (pin "1") (pinfunction "1_1") (pintype "passive"))
      (node (ref "C82") (pin "1") (pinfunction "1_1") (pintype "passive"))
      (node (ref "C83") (pin "1") (pinfunction "1_1") (pintype "passive"))
      (node (ref "C84") (pin "1") (pinfunction "1_1") (pintype "passive"))
      (node (ref "C85") (pin "1") (pinfunction "1_1") (pintype "passive"))
      (node (ref "C86") (pin "1") (pinfunction "1_1") (pintype "passive"))
      (node (ref "C87") (pin "1") (pinfunction "1_1") (pintype "passive"))
      (node (ref "C88") (pin "1") (pinfunction "1_1") (pintype "passive"))
      (node (ref "C89") (pin "1") (pinfunction "1_1") (pintype "passive"))
      (node (ref "C90") (pin "1") (pinfunction "1_1") (pintype "passive"))
      (node (ref "C91") (pin "1") (pinfunction "1_1") (pintype "passive"))
      (node (ref "C92") (pin "1") (pinfunction "1_1") (pintype "passive"))
      (node (ref "C93") (pin "1") (pinfunction "1_1") (pintype "passive"))
      (node (ref "C94") (pin "1") (pinfunction "1_1") (pintype "passive"))
      (node (ref "C95") (pin "1") (pinfunction "1_1") (pintype "passive"))
      (node (ref "C96") (pin "1") (pinfunction "1_1") (pintype "passive"))
      (node (ref "C97") (pin "1") (pinfunction "1_1") (pintype "passive"))
      (node (ref "C98") (pin "1") (pinfunction "1_1") (pintype "passive"))
      (node (ref "C99") (pin "1") (pinfunction "1_1") (pintype "passive"))
      (node (ref "D4") (pin "A12") (pinfunction "GND_A12") (pintype "power_in"))
      (node (ref "D4") (pin "A17") (pinfunction "GND_A17") (pintype "power_in"))
      (node (ref "D4") (pin "A27") (pinfunction "GND_A27") (pintype "power_in"))
      (node (ref "D4") (pin "AA1") (pinfunction "GND_AA1") (pintype "power_in"))
      (node (ref "D4") (pin "AA17") (pinfunction "GND_AA17") (pintype "power_in"))
      (node (ref "D4") (pin "AA2") (pinfunction "GND_AA2") (pintype "power_in"))
      (node (ref "D4") (pin "AA27") (pinfunction "GND_AA27") (pintype "power_in"))
      (node (ref "D4") (pin "AA3") (pinfunction "GND_AA3") (pintype "power_in"))
      (node (ref "D4") (pin "AA4") (pinfunction "GND_AA4") (pintype "power_in"))
      (node (ref "D4") (pin "AA6") (pinfunction "GND_AA6") (pintype "power_in"))
      (node (ref "D4") (pin "AB1") (pinfunction "GND_AB1") (pintype "power_in"))
      (node (ref "D4") (pin "AB10") (pinfunction "GND_AB10") (pintype "power_in"))
      (node (ref "D4") (pin "AB2") (pinfunction "GND_AB2") (pintype "power_in"))
      (node (ref "D4") (pin "AB20") (pinfunction "GND_AB20") (pintype "power_in"))
      (node (ref "D4") (pin "AB30") (pinfunction "GND_AB30") (pintype "power_in"))
      (node (ref "D4") (pin "AB5") (pinfunction "GND_AB5") (pintype "power_in"))
      (node (ref "D4") (pin "AC1") (pinfunction "GND_AC1") (pintype "power_in"))
      (node (ref "D4") (pin "AC13") (pinfunction "GND_AC13") (pintype "power_in"))
      (node (ref "D4") (pin "AC2") (pinfunction "GND_AC2") (pintype "power_in"))
      (node (ref "D4") (pin "AC23") (pinfunction "GND_AC23") (pintype "power_in"))
      (node (ref "D4") (pin "AC25") (pinfunction "VREFB5AN0_AC25") (pintype "power_in"))
      (node (ref "D4") (pin "AC3") (pinfunction "GND_AC3") (pintype "power_in"))
      (node (ref "D4") (pin "AC4") (pinfunction "GND_AC4") (pintype "power_in"))
      (node (ref "D4") (pin "AC6") (pinfunction "GND_AC6") (pintype "power_in"))
      (node (ref "D4") (pin "AD1") (pinfunction "GND_AD1") (pintype "power_in"))
      (node (ref "D4") (pin "AD16") (pinfunction "GND_AD16") (pintype "power_in"))
      (node (ref "D4") (pin "AD2") (pinfunction "GND_AD2") (pintype "power_in"))
      (node (ref "D4") (pin "AD26") (pinfunction "GND_AD26") (pintype "power_in"))
      (node (ref "D4") (pin "AD5") (pinfunction "GND_AD5") (pintype "power_in"))
      (node (ref "D4") (pin "AD7") (pinfunction "GND_AD7") (pintype "power_in"))
      (node (ref "D4") (pin "AE1") (pinfunction "GND_AE1") (pintype "power_in"))
      (node (ref "D4") (pin "AE19") (pinfunction "GND_AE19") (pintype "power_in"))
      (node (ref "D4") (pin "AE2") (pinfunction "GND_AE2") (pintype "power_in"))
      (node (ref "D4") (pin "AE29") (pinfunction "GND_AE29") (pintype "power_in"))
      (node (ref "D4") (pin "AE3") (pinfunction "GND_AE3") (pintype "power_in"))
      (node (ref "D4") (pin "AE4") (pinfunction "GND_AE4") (pintype "power_in"))
      (node (ref "D4") (pin "AE6") (pinfunction "GND_AE6") (pintype "power_in"))
      (node (ref "D4") (pin "AE8") (pinfunction "VREFB3AN0_AE8") (pintype "power_in"))
      (node (ref "D4") (pin "AE9") (pinfunction "GND_AE9") (pintype "power_in"))
      (node (ref "D4") (pin "AF1") (pinfunction "GND_AF1") (pintype "power_in"))
      (node (ref "D4") (pin "AF12") (pinfunction "GND_AF12") (pintype "power_in"))
      (node (ref "D4") (pin "AF2") (pinfunction "GND_AF2") (pintype "power_in"))
      (node (ref "D4") (pin "AF22") (pinfunction "GND_AF22") (pintype "power_in"))
      (node (ref "D4") (pin "AF5") (pinfunction "GND_AF5") (pintype "power_in"))
      (node (ref "D4") (pin "AG1") (pinfunction "GND_AG1") (pintype "power_in"))
      (node (ref "D4") (pin "AG15") (pinfunction "GND_AG15") (pintype "power_in"))
      (node (ref "D4") (pin "AG2") (pinfunction "GND_AG2") (pintype "power_in"))
      (node (ref "D4") (pin "AG25") (pinfunction "GND_AG25") (pintype "power_in"))
      (node (ref "D4") (pin "AG3") (pinfunction "GND_AG3") (pintype "power_in"))
      (node (ref "D4") (pin "AG4") (pinfunction "GND_AG4") (pintype "power_in"))
      (node (ref "D4") (pin "AH1") (pinfunction "GND_AH1") (pintype "power_in"))
      (node (ref "D4") (pin "AH18") (pinfunction "GND_AH18") (pintype "power_in"))
      (node (ref "D4") (pin "AH2") (pinfunction "GND_AH2") (pintype "power_in"))
      (node (ref "D4") (pin "AH28") (pinfunction "GND_AH28") (pintype "power_in"))
      (node (ref "D4") (pin "AH3") (pinfunction "GND_AH3") (pintype "power_in"))
      (node (ref "D4") (pin "AH8") (pinfunction "GND_AH8") (pintype "power_in"))
      (node (ref "D4") (pin "AJ11") (pinfunction "GND_AJ11") (pintype "power_in"))
      (node (ref "D4") (pin "AJ21") (pinfunction "GND_AJ21") (pintype "power_in"))
      (node (ref "D4") (pin "AJ6") (pinfunction "GND_AJ6") (pintype "power_in"))
      (node (ref "D4") (pin "AK14") (pinfunction "GND_AK14") (pintype "power_in"))
      (node (ref "D4") (pin "AK2") (pinfunction "GND_AK2") (pintype "power_in"))
      (node (ref "D4") (pin "AK24") (pinfunction "GND_AK24") (pintype "power_in"))
      (node (ref "D4") (pin "AK29") (pinfunction "GND_AK29") (pintype "power_in"))
      (node (ref "D4") (pin "B1") (pinfunction "GND_B1") (pintype "power_in"))
      (node (ref "D4") (pin "B10") (pinfunction "GND_B10") (pintype "power_in"))
      (node (ref "D4") (pin "B2") (pinfunction "GND_B2") (pintype "power_in"))
      (node (ref "D4") (pin "B20") (pinfunction "GND_B20") (pintype "power_in"))
      (node (ref "D4") (pin "B30") (pinfunction "GND_B30") (pintype "power_in"))
      (node (ref "D4") (pin "C13") (pinfunction "GND_C13") (pintype "power_in"))
      (node (ref "D4") (pin "C2") (pinfunction "GND_C2") (pintype "power_in"))
      (node (ref "D4") (pin "C23") (pinfunction "GND_C23") (pintype "power_in"))
      (node (ref "D4") (pin "C3") (pinfunction "GND_C3") (pintype "power_in"))
      (node (ref "D4") (pin "C4") (pinfunction "GND_C4") (pintype "power_in"))
      (node (ref "D4") (pin "D1") (pinfunction "GND_D1") (pintype "power_in"))
      (node (ref "D4") (pin "D16") (pinfunction "GND_D16") (pintype "power_in"))
      (node (ref "D4") (pin "D2") (pinfunction "GND_D2") (pintype "power_in"))
      (node (ref "D4") (pin "D26") (pinfunction "GND_D26") (pintype "power_in"))
      (node (ref "D4") (pin "D5") (pinfunction "GND_D5") (pintype "power_in"))
      (node (ref "D4") (pin "E19") (pinfunction "GND_E19") (pintype "power_in"))
      (node (ref "D4") (pin "E29") (pinfunction "GND_E29") (pintype "power_in"))
      (node (ref "D4") (pin "E3") (pinfunction "GND_E3") (pintype "power_in"))
      (node (ref "D4") (pin "E4") (pinfunction "GND_E4") (pintype "power_in"))
      (node (ref "D4") (pin "E5") (pinfunction "GND_E5") (pintype "power_in"))
      (node (ref "D4") (pin "E9") (pinfunction "GND_E9") (pintype "power_in"))
      (node (ref "D4") (pin "F1") (pinfunction "GND_F1") (pintype "power_in"))
      (node (ref "D4") (pin "F12") (pinfunction "GND_F12") (pintype "power_in"))
      (node (ref "D4") (pin "F2") (pinfunction "GND_F2") (pintype "power_in"))
      (node (ref "D4") (pin "F22") (pinfunction "GND_F22") (pintype "power_in"))
      (node (ref "D4") (pin "F5") (pinfunction "GND_F5") (pintype "power_in"))
      (node (ref "D4") (pin "G15") (pinfunction "GND_G15") (pintype "power_in"))
      (node (ref "D4") (pin "G24") (pinfunction "GND_G24") (pintype "power_in"))
      (node (ref "D4") (pin "G25") (pinfunction "GND_G25") (pintype "power_in"))
      (node (ref "D4") (pin "G3") (pinfunction "GND_G3") (pintype "power_in"))
      (node (ref "D4") (pin "G4") (pinfunction "GND_G4") (pintype "power_in"))
      (node (ref "D4") (pin "G5") (pinfunction "MSEL2_G5") (pintype "input"))
      (node (ref "D4") (pin "H1") (pinfunction "GND_H1") (pintype "power_in"))
      (node (ref "D4") (pin "H11") (pinfunction "GND_H11") (pintype "power_in"))
      (node (ref "D4") (pin "H18") (pinfunction "GND_H18") (pintype "power_in"))
      (node (ref "D4") (pin "H2") (pinfunction "GND_H2") (pintype "power_in"))
      (node (ref "D4") (pin "H28") (pinfunction "GND_H28") (pintype "power_in"))
      (node (ref "D4") (pin "H5") (pinfunction "GND_H5") (pintype "power_in"))
      (node (ref "D4") (pin "H6") (pinfunction "nCE_H6") (pintype "input"))
      (node (ref "D4") (pin "H8") (pinfunction "GND_H8") (pintype "power_in"))
      (node (ref "D4") (pin "J11") (pinfunction "GND_J11") (pintype "power_in"))
      (node (ref "D4") (pin "J21") (pinfunction "GND_J21") (pintype "power_in"))
      (node (ref "D4") (pin "J3") (pinfunction "GND_J3") (pintype "power_in"))
      (node (ref "D4") (pin "J4") (pinfunction "GND_J4") (pintype "power_in"))
      (node (ref "D4") (pin "J6") (pinfunction "GND_J6") (pintype "power_in"))
      (node (ref "D4") (pin "K1") (pinfunction "GND_K1") (pintype "power_in"))
      (node (ref "D4") (pin "K14") (pinfunction "GND_K14") (pintype "power_in"))
      (node (ref "D4") (pin "K2") (pinfunction "GND_K2") (pintype "power_in"))
      (node (ref "D4") (pin "K24") (pinfunction "GND_K24") (pintype "power_in"))
      (node (ref "D4") (pin "K5") (pinfunction "GND_K5") (pintype "power_in"))
      (node (ref "D4") (pin "K9") (pinfunction "GND_K9") (pintype "power_in"))
      (node (ref "D4") (pin "L1") (pinfunction "GND_L1") (pintype "power_in"))
      (node (ref "D4") (pin "L17") (pinfunction "GND_L17") (pintype "power_in"))
      (node (ref "D4") (pin "L2") (pinfunction "GND_L2") (pintype "power_in"))
      (node (ref "D4") (pin "L27") (pinfunction "GND_L27") (pintype "power_in"))
      (node (ref "D4") (pin "L3") (pinfunction "GND_L3") (pintype "power_in"))
      (node (ref "D4") (pin "L4") (pinfunction "GND_L4") (pintype "power_in"))
      (node (ref "D4") (pin "L6") (pinfunction "GND_L6") (pintype "power_in"))
      (node (ref "D4") (pin "M1") (pinfunction "GND_M1") (pintype "power_in"))
      (node (ref "D4") (pin "M10") (pinfunction "GND_M10") (pintype "power_in"))
      (node (ref "D4") (pin "M14") (pinfunction "GND_M14") (pintype "power_in"))
      (node (ref "D4") (pin "M16") (pinfunction "GND_M16") (pintype "power_in"))
      (node (ref "D4") (pin "M18") (pinfunction "GND_M18") (pintype "power_in"))
      (node (ref "D4") (pin "M2") (pinfunction "GND_M2") (pintype "power_in"))
      (node (ref "D4") (pin "M20") (pinfunction "GND_M20") (pintype "power_in"))
      (node (ref "D4") (pin "M26") (pinfunction "VREFB6AN0_M26") (pintype "power_in"))
      (node (ref "D4") (pin "M30") (pinfunction "GND_M30") (pintype "power_in"))
      (node (ref "D4") (pin "M5") (pinfunction "GND_M5") (pintype "power_in"))
      (node (ref "D4") (pin "N1") (pinfunction "GND_N1") (pintype "power_in"))
      (node (ref "D4") (pin "N13") (pinfunction "GND_N13") (pintype "power_in"))
      (node (ref "D4") (pin "N15") (pinfunction "GND_N15") (pintype "power_in"))
      (node (ref "D4") (pin "N17") (pinfunction "GND_N17") (pintype "power_in"))
      (node (ref "D4") (pin "N19") (pinfunction "GND_N19") (pintype "power_in"))
      (node (ref "D4") (pin "N2") (pinfunction "GND_N2") (pintype "power_in"))
      (node (ref "D4") (pin "N23") (pinfunction "GND_N23") (pintype "power_in"))
      (node (ref "D4") (pin "N3") (pinfunction "GND_N3") (pintype "power_in"))
      (node (ref "D4") (pin "N4") (pinfunction "GND_N4") (pintype "power_in"))
      (node (ref "D4") (pin "N6") (pinfunction "GND_N6") (pintype "power_in"))
      (node (ref "D4") (pin "N7") (pinfunction "GND_N7") (pintype "power_in"))
      (node (ref "D4") (pin "N8") (pinfunction "GND_N8") (pintype "power_in"))
      (node (ref "D4") (pin "P1") (pinfunction "GND_P1") (pintype "power_in"))
      (node (ref "D4") (pin "P11") (pinfunction "GND_P11") (pintype "power_in"))
      (node (ref "D4") (pin "P14") (pinfunction "GND_P14") (pintype "power_in"))
      (node (ref "D4") (pin "P16") (pinfunction "GND_P16") (pintype "power_in"))
      (node (ref "D4") (pin "P18") (pinfunction "GND_P18") (pintype "power_in"))
      (node (ref "D4") (pin "P2") (pinfunction "GND_P2") (pintype "power_in"))
      (node (ref "D4") (pin "P26") (pinfunction "GND_P26") (pintype "power_in"))
      (node (ref "D4") (pin "P27") (pinfunction "VREFB5BN0_P27") (pintype "power_in"))
      (node (ref "D4") (pin "P5") (pinfunction "GND_P5") (pintype "power_in"))
      (node (ref "D4") (pin "P7") (pinfunction "MSEL3_P7") (pintype "input"))
      (node (ref "D4") (pin "P8") (pinfunction "GND_P8") (pintype "power_in"))
      (node (ref "D4") (pin "R1") (pinfunction "GND_R1") (pintype "power_in"))
      (node (ref "D4") (pin "R13") (pinfunction "GND_R13") (pintype "power_in"))
      (node (ref "D4") (pin "R15") (pinfunction "GND_R15") (pintype "power_in"))
      (node (ref "D4") (pin "R17") (pinfunction "GND_R17") (pintype "power_in"))
      (node (ref "D4") (pin "R19") (pinfunction "GND_R19") (pintype "power_in"))
      (node (ref "D4") (pin "R2") (pinfunction "GND_R2") (pintype "power_in"))
      (node (ref "D4") (pin "R29") (pinfunction "GND_R29") (pintype "power_in"))
      (node (ref "D4") (pin "R3") (pinfunction "GND_R3") (pintype "power_in"))
      (node (ref "D4") (pin "R4") (pinfunction "GND_R4") (pintype "power_in"))
      (node (ref "D4") (pin "R6") (pinfunction "GND_R6") (pintype "power_in"))
      (node (ref "D4") (pin "R7") (pinfunction "GND_R7") (pintype "power_in"))
      (node (ref "D4") (pin "R8") (pinfunction "GND_R8") (pintype "power_in"))
      (node (ref "D4") (pin "R9") (pinfunction "GND_R9") (pintype "power_in"))
      (node (ref "D4") (pin "T1") (pinfunction "GND_T1") (pintype "power_in"))
      (node (ref "D4") (pin "T12") (pinfunction "GND_T12") (pintype "power_in"))
      (node (ref "D4") (pin "T14") (pinfunction "GND_T14") (pintype "power_in"))
      (node (ref "D4") (pin "T16") (pinfunction "GND_T16") (pintype "power_in"))
      (node (ref "D4") (pin "T18") (pinfunction "GND_T18") (pintype "power_in"))
      (node (ref "D4") (pin "T2") (pinfunction "GND_T2") (pintype "power_in"))
      (node (ref "D4") (pin "T20") (pinfunction "GND_T20") (pintype "power_in"))
      (node (ref "D4") (pin "T22") (pinfunction "GND_T22") (pintype "power_in"))
      (node (ref "D4") (pin "T5") (pinfunction "GND_T5") (pintype "power_in"))
      (node (ref "D4") (pin "T8") (pinfunction "MSEL0_T8") (pintype "input"))
      (node (ref "D4") (pin "U1") (pinfunction "GND_U1") (pintype "power_in"))
      (node (ref "D4") (pin "U13") (pinfunction "GND_U13") (pintype "power_in"))
      (node (ref "D4") (pin "U15") (pinfunction "GND_U15") (pintype "power_in"))
      (node (ref "D4") (pin "U17") (pinfunction "GND_U17") (pintype "power_in"))
      (node (ref "D4") (pin "U19") (pinfunction "GND_U19") (pintype "power_in"))
      (node (ref "D4") (pin "U2") (pinfunction "GND_U2") (pintype "power_in"))
      (node (ref "D4") (pin "U25") (pinfunction "GND_U25") (pintype "power_in"))
      (node (ref "D4") (pin "U3") (pinfunction "GND_U3") (pintype "power_in"))
      (node (ref "D4") (pin "U4") (pinfunction "GND_U4") (pintype "power_in"))
      (node (ref "D4") (pin "U6") (pinfunction "GND_U6") (pintype "power_in"))
      (node (ref "D4") (pin "V1") (pinfunction "GND_V1") (pintype "power_in"))
      (node (ref "D4") (pin "V14") (pinfunction "GND_V14") (pintype "power_in"))
      (node (ref "D4") (pin "V16") (pinfunction "GND_V16") (pintype "power_in"))
      (node (ref "D4") (pin "V18") (pinfunction "GND_V18") (pintype "power_in"))
      (node (ref "D4") (pin "V2") (pinfunction "GND_V2") (pintype "power_in"))
      (node (ref "D4") (pin "V20") (pinfunction "GND_V20") (pintype "power_in"))
      (node (ref "D4") (pin "V23") (pinfunction "GND_V23") (pintype "power_in"))
      (node (ref "D4") (pin "V28") (pinfunction "GND_V28") (pintype "power_in"))
      (node (ref "D4") (pin "V5") (pinfunction "GND_V5") (pintype "power_in"))
      (node (ref "D4") (pin "V8") (pinfunction "GND_V8") (pintype "power_in"))
      (node (ref "D4") (pin "W1") (pinfunction "GND_W1") (pintype "power_in"))
      (node (ref "D4") (pin "W11") (pinfunction "GND_W11") (pintype "power_in"))
      (node (ref "D4") (pin "W13") (pinfunction "GND_W13") (pintype "power_in"))
      (node (ref "D4") (pin "W15") (pinfunction "GND_W15") (pintype "power_in"))
      (node (ref "D4") (pin "W17") (pinfunction "GND_W17") (pintype "power_in"))
      (node (ref "D4") (pin "W19") (pinfunction "GND_W19") (pintype "power_in"))
      (node (ref "D4") (pin "W2") (pinfunction "GND_W2") (pintype "power_in"))
      (node (ref "D4") (pin "W21") (pinfunction "GND_W21") (pintype "power_in"))
      (node (ref "D4") (pin "W3") (pinfunction "GND_W3") (pintype "power_in"))
      (node (ref "D4") (pin "W4") (pinfunction "GND_W4") (pintype "power_in"))
      (node (ref "D4") (pin "W6") (pinfunction "GND_W6") (pintype "power_in"))
      (node (ref "D4") (pin "W7") (pinfunction "GND_W7") (pintype "power_in"))
      (node (ref "D4") (pin "W8") (pinfunction "GND_W8") (pintype "power_in"))
      (node (ref "D4") (pin "Y1") (pinfunction "GND_Y1") (pintype "power_in"))
      (node (ref "D4") (pin "Y14") (pinfunction "GND_Y14") (pintype "power_in"))
      (node (ref "D4") (pin "Y2") (pinfunction "GND_Y2") (pintype "power_in"))
      (node (ref "D4") (pin "Y24") (pinfunction "GND_Y24") (pintype "power_in"))
      (node (ref "D4") (pin "Y5") (pinfunction "GND_Y5") (pintype "power_in"))
      (node (ref "D4") (pin "Y7") (pinfunction "GND_Y7") (pintype "power_in"))
      (node (ref "R33") (pin "1") (pinfunction "1_1") (pintype "passive"))
      (node (ref "X1") (pin "10") (pintype "passive"))
      (node (ref "X1") (pin "2") (pintype "passive"))
    )
    (net (code "2") (name "/Fpga_CONF_DONE") (class "Default")
      (node (ref "D4") (pin "L8") (pinfunction "CONF_DONE_L8") (pintype "bidirectional"))
      (node (ref "R31") (pin "2") (pinfunction "2_2") (pintype "passive"))
    )
    (net (code "3") (name "/Fpga_DCLK") (class "Default")
      (node (ref "D4") (pin "T7") (pinfunction "DCLK_T7") (pintype "bidirectional"))
      (node (ref "R32") (pin "2") (pinfunction "2_2") (pintype "passive"))
    )
    (net (code "4") (name "/Fpga_Data0") (class "Default")
      (node (ref "D4") (pin "AG5") (pinfunction "AS_DATA0,_ASDO,_DATA0_AG5") (pintype "bidirectional"))
    )
    (net (code "5") (name "/Fpga_nCONFIG") (class "Default")
      (node (ref "D4") (pin "C5") (pinfunction "nCONFIG_C5") (pintype "input"))
      (node (ref "R30") (pin "2") (pinfunction "2_2") (pintype "passive"))
    )
    (net (code "6") (name "/Fpga_nSTATUS") (class "Default")
      (node (ref "D4") (pin "K7") (pinfunction "nSTATUS_K7") (pintype "bidirectional"))
    )
    (net (code "7") (name "/TCK") (class "Default")
      (node (ref "D4") (pin "AC7") (pinfunction "TCK_AC7") (pintype "input"))
      (node (ref "R26") (pin "2") (pinfunction "2_2") (pintype "passive"))
      (node (ref "R33") (pin "2") (pinfunction "2_2") (pintype "passive"))
      (node (ref "X1") (pin "1") (pintype "passive"))
    )
    (net (code "8") (name "/TDI") (class "Default")
      (node (ref "D4") (pin "U7") (pinfunction "TDI_U7") (pintype "input"))
      (node (ref "R27") (pin "1") (pinfunction "1_1") (pintype "passive"))
      (node (ref "X1") (pin "9") (pintype "passive"))
    )
    (net (code "9") (name "/TDO") (class "Default")
      (node (ref "D4") (pin "W9") (pinfunction "TDO_W9") (pintype "output"))
      (node (ref "X1") (pin "3") (pintype "passive"))
    )
    (net (code "10") (name "/TMS") (class "Default")
      (node (ref "D4") (pin "V7") (pinfunction "TMS_V7") (pintype "input"))
      (node (ref "R25") (pin "2") (pinfunction "2_2") (pintype "passive"))
      (node (ref "X1") (pin "5") (pintype "passive"))
    )
    (net (code "11") (name "/v1p1d") (class "Default")
      (node (ref "C63") (pin "2") (pinfunction "2_2") (pintype "passive"))
      (node (ref "C64") (pin "2") (pinfunction "2_2") (pintype "passive"))
      (node (ref "C65") (pin "2") (pinfunction "2_2") (pintype "passive"))
      (node (ref "C66") (pin "2") (pinfunction "2_2") (pintype "passive"))
      (node (ref "C67") (pin "2") (pinfunction "2_2") (pintype "passive"))
      (node (ref "C68") (pin "2") (pinfunction "2_2") (pintype "passive"))
      (node (ref "C69") (pin "2") (pinfunction "2_2") (pintype "passive"))
      (node (ref "C75") (pin "2") (pinfunction "2_2") (pintype "passive"))
      (node (ref "C76") (pin "2") (pinfunction "2_2") (pintype "passive"))
      (node (ref "C77") (pin "2") (pinfunction "2_2") (pintype "passive"))
      (node (ref "C78") (pin "2") (pinfunction "2_2") (pintype "passive"))
      (node (ref "C79") (pin "2") (pinfunction "2_2") (pintype "passive"))
      (node (ref "C80") (pin "2") (pinfunction "2_2") (pintype "passive"))
      (node (ref "C81") (pin "2") (pinfunction "2_2") (pintype "passive"))
      (node (ref "C87") (pin "2") (pinfunction "2_2") (pintype "passive"))
      (node (ref "C88") (pin "2") (pinfunction "2_2") (pintype "passive"))
      (node (ref "C89") (pin "2") (pinfunction "2_2") (pintype "passive"))
      (node (ref "C90") (pin "2") (pinfunction "2_2") (pintype "passive"))
      (node (ref "C91") (pin "2") (pinfunction "2_2") (pintype "passive"))
      (node (ref "C92") (pin "2") (pinfunction "2_2") (pintype "passive"))
      (node (ref "C93") (pin "2") (pinfunction "2_2") (pintype "passive"))
      (node (ref "C94") (pin "2") (pinfunction "2_2") (pintype "passive"))
      (node (ref "D4") (pin "AA5") (pinfunction "VCC_AA5") (pintype "power_in"))
      (node (ref "D4") (pin "AC5") (pinfunction "VCC_AC5") (pintype "power_in"))
      (node (ref "D4") (pin "AD6") (pinfunction "VCC_AD6") (pintype "power_in"))
      (node (ref "D4") (pin "J5") (pinfunction "VCC_J5") (pintype "power_in"))
      (node (ref "D4") (pin "L5") (pinfunction "VCC_L5") (pintype "power_in"))
      (node (ref "D4") (pin "M13") (pinfunction "VCC_M13") (pintype "power_in"))
      (node (ref "D4") (pin "M15") (pinfunction "VCC_M15") (pintype "power_in"))
      (node (ref "D4") (pin "M17") (pinfunction "VCC_M17") (pintype "power_in"))
      (node (ref "D4") (pin "M19") (pinfunction "VCC_M19") (pintype "power_in"))
      (node (ref "D4") (pin "M6") (pinfunction "VCC_M6") (pintype "power_in"))
      (node (ref "D4") (pin "N14") (pinfunction "VCC_N14") (pintype "power_in"))
      (node (ref "D4") (pin "N16") (pinfunction "VCC_N16") (pintype "power_in"))
      (node (ref "D4") (pin "N18") (pinfunction "VCC_N18") (pintype "power_in"))
      (node (ref "D4") (pin "N5") (pinfunction "VCC_N5") (pintype "power_in"))
      (node (ref "D4") (pin "P13") (pinfunction "VCC_P13") (pintype "power_in"))
      (node (ref "D4") (pin "P15") (pinfunction "VCC_P15") (pintype "power_in"))
      (node (ref "D4") (pin "P17") (pinfunction "VCC_P17") (pintype "power_in"))
      (node (ref "D4") (pin "P19") (pinfunction "VCC_P19") (pintype "power_in"))
      (node (ref "D4") (pin "R14") (pinfunction "VCC_R14") (pintype "power_in"))
      (node (ref "D4") (pin "R16") (pinfunction "VCC_R16") (pintype "power_in"))
      (node (ref "D4") (pin "R18") (pinfunction "VCC_R18") (pintype "power_in"))
      (node (ref "D4") (pin "R5") (pinfunction "VCC_R5") (pintype "power_in"))
      (node (ref "D4") (pin "T13") (pinfunction "VCC_T13") (pintype "power_in"))
      (node (ref "D4") (pin "T15") (pinfunction "VCC_T15") (pintype "power_in"))
      (node (ref "D4") (pin "T17") (pinfunction "VCC_T17") (pintype "power_in"))
      (node (ref "D4") (pin "T19") (pinfunction "VCC_T19") (pintype "power_in"))
      (node (ref "D4") (pin "T6") (pinfunction "VCC_T6") (pintype "power_in"))
      (node (ref "D4") (pin "U14") (pinfunction "VCC_U14") (pintype "power_in"))
      (node (ref "D4") (pin "U16") (pinfunction "VCC_U16") (pintype "power_in"))
      (node (ref "D4") (pin "U18") (pinfunction "VCC_U18") (pintype "power_in"))
      (node (ref "D4") (pin "U20") (pinfunction "VCC_U20") (pintype "power_in"))
      (node (ref "D4") (pin "U5") (pinfunction "VCC_U5") (pintype "power_in"))
      (node (ref "D4") (pin "V13") (pinfunction "VCC_V13") (pintype "power_in"))
      (node (ref "D4") (pin "V15") (pinfunction "VCC_V15") (pintype "power_in"))
      (node (ref "D4") (pin "V17") (pinfunction "VCC_V17") (pintype "power_in"))
      (node (ref "D4") (pin "V19") (pinfunction "VCC_V19") (pintype "power_in"))
      (node (ref "D4") (pin "W14") (pinfunction "VCC_W14") (pintype "power_in"))
      (node (ref "D4") (pin "W16") (pinfunction "VCC_W16") (pintype "power_in"))
      (node (ref "D4") (pin "W18") (pinfunction "VCC_W18") (pintype "power_in"))
      (node (ref "D4") (pin "W20") (pinfunction "VCC_W20") (pintype "power_in"))
      (node (ref "D4") (pin "W5") (pinfunction "VCC_W5") (pintype "power_in"))
      (node (ref "D4") (pin "Y6") (pinfunction "VCC_Y6") (pintype "power_in"))
    )
    (net (code "12") (name "/v1p5d") (class "Default")
      (node (ref "C111") (pin "2") (pinfunction "2_2") (pintype "passive"))
      (node (ref "C112") (pin "2") (pinfunction "2_2") (pintype "passive"))
      (node (ref "C113") (pin "2") (pinfunction "2_2") (pintype "passive"))
      (node (ref "C114") (pin "2") (pinfunction "2_2") (pintype "passive"))
      (node (ref "C115") (pin "2") (pinfunction "2_2") (pintype "passive"))
      (node (ref "C116") (pin "2") (pinfunction "2_2") (pintype "passive"))
      (node (ref "C117") (pin "2") (pinfunction "2_2") (pintype "passive"))
      (node (ref "C124") (pin "2") (pinfunction "2_2") (pintype "passive"))
      (node (ref "C125") (pin "2") (pinfunction "2_2") (pintype "passive"))
      (node (ref "C126") (pin "2") (pinfunction "2_2") (pintype "passive"))
      (node (ref "C127") (pin "2") (pinfunction "2_2") (pintype "passive"))
      (node (ref "C128") (pin "2") (pinfunction "2_2") (pintype "passive"))
      (node (ref "C129") (pin "2") (pinfunction "2_2") (pintype "passive"))
      (node (ref "C130") (pin "2") (pinfunction "2_2") (pintype "passive"))
      (node (ref "C135") (pin "2") (pinfunction "2_2") (pintype "passive"))
      (node (ref "C136") (pin "2") (pinfunction "2_2") (pintype "passive"))
      (node (ref "C137") (pin "2") (pinfunction "2_2") (pintype "passive"))
      (node (ref "C138") (pin "2") (pinfunction "2_2") (pintype "passive"))
      (node (ref "D4") (pin "A22") (pinfunction "VCCIO7A_A22") (pintype "power_in"))
      (node (ref "D4") (pin "A7") (pinfunction "VCCIO8A_A7") (pintype "power_in"))
      (node (ref "D4") (pin "AA12") (pinfunction "VCCIO3B_AA12") (pintype "power_in"))
      (node (ref "D4") (pin "AB15") (pinfunction "VCCIO4A_AB15") (pintype "power_in"))
      (node (ref "D4") (pin "AC18") (pinfunction "VCCIO4A_AC18") (pintype "power_in"))
      (node (ref "D4") (pin "AD21") (pinfunction "VCCIO4A_AD21") (pintype "power_in"))
      (node (ref "D4") (pin "AE14") (pinfunction "VCCIO3B_AE14") (pintype "power_in"))
      (node (ref "D4") (pin "AF17") (pinfunction "VCCIO4A_AF17") (pintype "power_in"))
      (node (ref "D4") (pin "AG10") (pinfunction "VCCIO3B_AG10") (pintype "power_in"))
      (node (ref "D4") (pin "AG20") (pinfunction "VCCIO4A_AG20") (pintype "power_in"))
      (node (ref "D4") (pin "AH13") (pinfunction "VCCIO3B_AH13") (pintype "power_in"))
      (node (ref "D4") (pin "AH23") (pinfunction "VCCIO4A_AH23") (pintype "power_in"))
      (node (ref "D4") (pin "AJ16") (pinfunction "VCCIO4A_AJ16") (pintype "power_in"))
      (node (ref "D4") (pin "AJ26") (pinfunction "VCCIO4A_AJ26") (pintype "power_in"))
      (node (ref "D4") (pin "AK19") (pinfunction "VCCIO4A_AK19") (pintype "power_in"))
      (node (ref "D4") (pin "AK4") (pinfunction "VCCIO3B_AK4") (pintype "power_in"))
      (node (ref "D4") (pin "AK9") (pinfunction "VCCIO3B_AK9") (pintype "power_in"))
      (node (ref "D4") (pin "B15") (pinfunction "VCCIO7A_B15") (pintype "power_in"))
      (node (ref "D4") (pin "B25") (pinfunction "VCCIO7A_B25") (pintype "power_in"))
      (node (ref "D4") (pin "B5") (pinfunction "VCCIO8A_B5") (pintype "power_in"))
      (node (ref "D4") (pin "C18") (pinfunction "VCCIO7A_C18") (pintype "power_in"))
      (node (ref "D4") (pin "C8") (pinfunction "VCCIO8A_C8") (pintype "power_in"))
      (node (ref "D4") (pin "D11") (pinfunction "VCCIO8A_D11") (pintype "power_in"))
      (node (ref "D4") (pin "D21") (pinfunction "VCCIO7A_D21") (pintype "power_in"))
      (node (ref "D4") (pin "E14") (pinfunction "VCCIO8A_E14") (pintype "power_in"))
      (node (ref "D4") (pin "E24") (pinfunction "VCCIO7A_E24") (pintype "power_in"))
      (node (ref "D4") (pin "F17") (pinfunction "VCCIO7A_F17") (pintype "power_in"))
      (node (ref "D4") (pin "F7") (pinfunction "VCCIO8A_F7") (pintype "power_in"))
      (node (ref "D4") (pin "G10") (pinfunction "VCCIO8A_G10") (pintype "power_in"))
      (node (ref "D4") (pin "G20") (pinfunction "VCCIO7A_G20") (pintype "power_in"))
      (node (ref "D4") (pin "H10") (pinfunction "VCCBAT_H10") (pintype "power_in"))
      (node (ref "D4") (pin "H13") (pinfunction "VCCIO8A_H13") (pintype "power_in"))
      (node (ref "D4") (pin "H23") (pinfunction "VCCIO7A_H23") (pintype "power_in"))
      (node (ref "D4") (pin "J16") (pinfunction "VCCIO8A_J16") (pintype "power_in"))
      (node (ref "D4") (pin "K19") (pinfunction "VCCIO7A_K19") (pintype "power_in"))
      (node (ref "D4") (pin "L12") (pinfunction "VCCIO8A_L12") (pintype "power_in"))
      (node (ref "D4") (pin "Y19") (pinfunction "VCCIO4A_Y19") (pintype "power_in"))
    )
    (net (code "13") (name "/v1p8d") (class "Default")
      (node (ref "L5") (pin "2") (pinfunction "2_2") (pintype "passive"))
    )
    (net (code "14") (name "/v2p5d") (class "Default")
      (node (ref "C100") (pin "2") (pinfunction "2_2") (pintype "passive"))
      (node (ref "C101") (pin "2") (pinfunction "2_2") (pintype "passive"))
      (node (ref "C102") (pin "2") (pinfunction "2_2") (pintype "passive"))
      (node (ref "C103") (pin "2") (pinfunction "2_2") (pintype "passive"))
      (node (ref "C104") (pin "2") (pinfunction "2_2") (pintype "passive"))
      (node (ref "C105") (pin "2") (pinfunction "2_2") (pintype "passive"))
      (node (ref "C106") (pin "2") (pinfunction "2_2") (pintype "passive"))
      (node (ref "C107") (pin "2") (pinfunction "2_2") (pintype "passive"))
      (node (ref "C108") (pin "2") (pinfunction "2_2") (pintype "passive"))
      (node (ref "C122") (pin "2") (pinfunction "2_2") (pintype "passive"))
      (node (ref "C123") (pin "2") (pinfunction "2_2") (pintype "passive"))
      (node (ref "C131") (pin "2") (pinfunction "2_2") (pintype "passive"))
      (node (ref "C132") (pin "2") (pinfunction "2_2") (pintype "passive"))
      (node (ref "C133") (pin "2") (pinfunction "2_2") (pintype "passive"))
      (node (ref "C134") (pin "2") (pinfunction "2_2") (pintype "passive"))
      (node (ref "C139") (pin "2") (pinfunction "2_2") (pintype "passive"))
      (node (ref "C140") (pin "2") (pinfunction "2_2") (pintype "passive"))
      (node (ref "C141") (pin "2") (pinfunction "2_2") (pintype "passive"))
      (node (ref "C142") (pin "2") (pinfunction "2_2") (pintype "passive"))
      (node (ref "C97") (pin "2") (pinfunction "2_2") (pintype "passive"))
      (node (ref "C98") (pin "2") (pinfunction "2_2") (pintype "passive"))
      (node (ref "C99") (pin "2") (pinfunction "2_2") (pintype "passive"))
      (node (ref "D4") (pin "AA22") (pinfunction "VCCIO5A_AA22") (pintype "power_in"))
      (node (ref "D4") (pin "AB11") (pinfunction "VCCPD3A_AB11") (pintype "power_in"))
      (node (ref "D4") (pin "AB25") (pinfunction "VCCIO5A_AB25") (pintype "power_in"))
      (node (ref "D4") (pin "AC12") (pinfunction "VCCPD3B4A_AC12") (pintype "power_in"))
      (node (ref "D4") (pin "AC17") (pinfunction "VCCPD3B4A_AC17") (pintype "power_in"))
      (node (ref "D4") (pin "AC20") (pinfunction "VCCPD3B4A_AC20") (pintype "power_in"))
      (node (ref "D4") (pin "AC28") (pinfunction "VCCIO5B_AC28") (pintype "power_in"))
      (node (ref "D4") (pin "AD10") (pinfunction "VCCPD3A_AD10") (pintype "power_in"))
      (node (ref "D4") (pin "AD15") (pinfunction "VCCPD3B4A_AD15") (pintype "power_in"))
      (node (ref "D4") (pin "AE11") (pinfunction "VCCPD3B4A_AE11") (pintype "power_in"))
      (node (ref "D4") (pin "AE21") (pinfunction "VCCPD3B4A_AE21") (pintype "power_in"))
      (node (ref "D4") (pin "AE24") (pinfunction "VCCIO5A_AE24") (pintype "power_in"))
      (node (ref "D4") (pin "AF27") (pinfunction "VCCIO5A_AF27") (pintype "power_in"))
      (node (ref "D4") (pin "AG30") (pinfunction "VCCIO5B_AG30") (pintype "power_in"))
      (node (ref "D4") (pin "C28") (pinfunction "VCCIO6A_C28") (pintype "power_in"))
      (node (ref "D4") (pin "D24") (pinfunction "VCCPD7A8A_D24") (pintype "power_in"))
      (node (ref "D4") (pin "F11") (pinfunction "VCCPD7A8A_F11") (pintype "power_in"))
      (node (ref "D4") (pin "F21") (pinfunction "VCCPD7A8A_F21") (pintype "power_in"))
      (node (ref "D4") (pin "F23") (pinfunction "VCCPD7A8A_F23") (pintype "power_in"))
      (node (ref "D4") (pin "F27") (pinfunction "VCCIO6A_F27") (pintype "power_in"))
      (node (ref "D4") (pin "G13") (pinfunction "VCCPD7A8A_G13") (pintype "power_in"))
      (node (ref "D4") (pin "G16") (pinfunction "VCCPD7A8A_G16") (pintype "power_in"))
      (node (ref "D4") (pin "G19") (pinfunction "VCCPD7A8A_G19") (pintype "power_in"))
      (node (ref "D4") (pin "G30") (pinfunction "VCCIO6A_G30") (pintype "power_in"))
      (node (ref "D4") (pin "J26") (pinfunction "VCCIO6A_J26") (pintype "power_in"))
      (node (ref "D4") (pin "K23") (pinfunction "VCCPD6A_K23") (pintype "power_in"))
      (node (ref "D4") (pin "K29") (pinfunction "VCCIO6A_K29") (pintype "power_in"))
      (node (ref "D4") (pin "L22") (pinfunction "VCCIO6A_L22") (pintype "power_in"))
      (node (ref "D4") (pin "M24") (pinfunction "VCCPD6A_M24") (pintype "power_in"))
      (node (ref "D4") (pin "M25") (pinfunction "VCCIO6A_M25") (pintype "power_in"))
      (node (ref "D4") (pin "N28") (pinfunction "VCCIO6A_N28") (pintype "power_in"))
      (node (ref "D4") (pin "P21") (pinfunction "VCCIO6A_P21") (pintype "power_in"))
      (node (ref "D4") (pin "P24") (pinfunction "VCCPD6A_P24") (pintype "power_in"))
      (node (ref "D4") (pin "R24") (pinfunction "VCCIO6A_R24") (pintype "power_in"))
      (node (ref "D4") (pin "T26") (pinfunction "VCCPD5B_T26") (pintype "power_in"))
      (node (ref "D4") (pin "T27") (pinfunction "VCCIO5B_T27") (pintype "power_in"))
      (node (ref "D4") (pin "U24") (pinfunction "VCCPD5B_U24") (pintype "power_in"))
      (node (ref "D4") (pin "U30") (pinfunction "VCCIO5B_U30") (pintype "power_in"))
      (node (ref "D4") (pin "W23") (pinfunction "VCCPD5A_W23") (pintype "power_in"))
      (node (ref "D4") (pin "W25") (pinfunction "VCCPD5A_W25") (pintype "power_in"))
      (node (ref "D4") (pin "W26") (pinfunction "VCCIO5B_W26") (pintype "power_in"))
      (node (ref "D4") (pin "Y29") (pinfunction "VCCIO5B_Y29") (pintype "power_in"))
      (node (ref "L3") (pin "2") (pinfunction "2_2") (pintype "passive"))
      (node (ref "L4") (pin "2") (pinfunction "2_2") (pintype "passive"))
    )
    (net (code "15") (name "/vRefDDR0") (class "Default")
      (node (ref "C118") (pin "2") (pinfunction "2_2") (pintype "passive"))
      (node (ref "C119") (pin "2") (pinfunction "2_2") (pintype "passive"))
      (node (ref "D4") (pin "AH16") (pinfunction "VREFB4AN0_AH16") (pintype "power_in"))
      (node (ref "D4") (pin "AJ13") (pinfunction "VREFB3BN0_AJ13") (pintype "power_in"))
    )
    (net (code "16") (name "/vRefDDR1") (class "Default")
      (node (ref "C120") (pin "2") (pinfunction "2_2") (pintype "passive"))
      (node (ref "C121") (pin "2") (pinfunction "2_2") (pintype "passive"))
      (node (ref "D4") (pin "B16") (pinfunction "VREFB7AN0_B16") (pintype "power_in"))
      (node (ref "D4") (pin "B9") (pinfunction "VREFB8AN0_B9") (pintype "power_in"))
    )
    (net (code "17") (name "/vcc_aux") (class "Default")
      (node (ref "C82") (pin "2") (pinfunction "2_2") (pintype "passive"))
      (node (ref "C83") (pin "2") (pinfunction "2_2") (pintype "passive"))
      (node (ref "C84") (pin "2") (pinfunction "2_2") (pintype "passive"))
      (node (ref "C85") (pin "2") (pinfunction "2_2") (pintype "passive"))
      (node (ref "C86") (pin "2") (pinfunction "2_2") (pintype "passive"))
      (node (ref "D4") (pin "AC10") (pinfunction "VCC_AUX_AC10") (pintype "power_in"))
      (node (ref "D4") (pin "AC16") (pinfunction "VCC_AUX_AC16") (pintype "power_in"))
      (node (ref "D4") (pin "AD22") (pinfunction "VCC_AUX_AD22") (pintype "power_in"))
      (node (ref "D4") (pin "G11") (pinfunction "VCC_AUX_G11") (pintype "power_in"))
      (node (ref "D4") (pin "H16") (pinfunction "VCC_AUX_H16") (pintype "power_in"))
      (node (ref "D4") (pin "H22") (pinfunction "VCC_AUX_H22") (pintype "power_in"))
      (node (ref "L4") (pin "1") (pinfunction "1_1") (pintype "passive"))
    )
    (net (code "18") (name "/vccpgm") (class "Default")
      (node (ref "C109") (pin "2") (pinfunction "2_2") (pintype "passive"))
      (node (ref "C110") (pin "2") (pinfunction "2_2") (pintype "passive"))
      (node (ref "C95") (pin "2") (pinfunction "2_2") (pintype "passive"))
      (node (ref "C96") (pin "2") (pinfunction "2_2") (pintype "passive"))
      (node (ref "D4") (pin "AB24") (pinfunction "VCCPGM_AB24") (pintype "power_in"))
      (node (ref "D4") (pin "AC11") (pinfunction "VCCPGM_AC11") (pintype "power_in"))
      (node (ref "D4") (pin "AC8") (pinfunction "VCCIO3A_AC8") (pintype "power_in"))
      (node (ref "D4") (pin "AD11") (pinfunction "VCCIO3A_AD11") (pintype "power_in"))
      (node (ref "D4") (pin "F10") (pinfunction "VCCPGM_F10") (pintype "power_in"))
      (node (ref "D4") (pin "U10") (pinfunction "VCCIO3A_U10") (pintype "power_in"))
      (node (ref "D4") (pin "Y9") (pinfunction "VCCIO3A_Y9") (pintype "power_in"))
      (node (ref "L5") (pin "1") (pinfunction "1_1") (pintype "passive"))
      (node (ref "R25") (pin "1") (pinfunction "1_1") (pintype "passive"))
      (node (ref "R26") (pin "1") (pinfunction "1_1") (pintype "passive"))
      (node (ref "R27") (pin "2") (pinfunction "2_2") (pintype "passive"))
      (node (ref "R28") (pin "2") (pinfunction "2_2") (pintype "passive"))
      (node (ref "R29") (pin "2") (pinfunction "2_2") (pintype "passive"))
      (node (ref "R30") (pin "1") (pinfunction "1_1") (pintype "passive"))
      (node (ref "R31") (pin "1") (pinfunction "1_1") (pintype "passive"))
      (node (ref "R32") (pin "1") (pinfunction "1_1") (pintype "passive"))
      (node (ref "X1") (pin "4") (pintype "passive"))
    )
    (net (code "19") (name "Net-(C70-Pad2)") (class "Default")
      (node (ref "C70") (pin "2") (pinfunction "2_2") (pintype "passive"))
      (node (ref "C71") (pin "2") (pinfunction "2_2") (pintype "passive"))
      (node (ref "C72") (pin "2") (pinfunction "2_2") (pintype "passive"))
      (node (ref "C73") (pin "2") (pinfunction "2_2") (pintype "passive"))
      (node (ref "C74") (pin "2") (pinfunction "2_2") (pintype "passive"))
      (node (ref "D4") (pin "AB23") (pinfunction "VCCA_FPLL_AB23") (pintype "power_in"))
      (node (ref "D4") (pin "AB6") (pinfunction "VCCA_FPLL_AB6") (pintype "power_in"))
      (node (ref "D4") (pin "J24") (pinfunction "VCCA_FPLL_J24") (pintype "power_in"))
      (node (ref "D4") (pin "J8") (pinfunction "VCCA_FPLL_J8") (pintype "power_in"))
      (node (ref "D4") (pin "K6") (pinfunction "VCCA_FPLL_K6") (pintype "power_in"))
      (node (ref "D4") (pin "P6") (pinfunction "VCCA_FPLL_P6") (pintype "power_in"))
      (node (ref "D4") (pin "V6") (pinfunction "VCCA_FPLL_V6") (pintype "power_in"))
      (node (ref "D4") (pin "Y8") (pinfunction "VCCA_FPLL_Y8") (pintype "power_in"))
      (node (ref "L3") (pin "1") (pinfunction "1_1") (pintype "passive"))
    )
    (net (code "20") (name "Net-(D4I-MSEL1)") (class "Default")
      (node (ref "D4") (pin "P9") (pinfunction "MSEL1_P9") (pintype "input"))
      (node (ref "R28") (pin "1") (pinfunction "1_1") (pintype "passive"))
    )
    (net (code "21") (name "Net-(D4I-MSEL4)") (class "Default")
      (node (ref "D4") (pin "M7") (pinfunction "MSEL4_M7") (pintype "input"))
      (node (ref "R29") (pin "1") (pinfunction "1_1") (pintype "passive"))
    )
    (net (code "22") (name "unconnected-(C120-Pad1)") (class "Default")
      (node (ref "C120") (pin "1") (pinfunction "1_1") (pintype "passive"))
    )
    (net (code "23") (name "unconnected-(C121-Pad1)") (class "Default")
      (node (ref "C121") (pin "1") (pinfunction "1_1") (pintype "passive"))
    )
    (net (code "24") (name "unconnected-(D4I-AS_DATA1,_DATA1-PadAE5)") (class "Default")
      (node (ref "D4") (pin "AE5") (pinfunction "AS_DATA1,_DATA1_AE5") (pintype "bidirectional"))
    )
    (net (code "25") (name "unconnected-(D4I-AS_DATA2,_DATA2-PadAE7)") (class "Default")
      (node (ref "D4") (pin "AE7") (pinfunction "AS_DATA2,_DATA2_AE7") (pintype "bidirectional"))
    )
    (net (code "26") (name "unconnected-(D4I-AS_DATA3,_DATA3-PadAB7)") (class "Default")
      (node (ref "D4") (pin "AB7") (pinfunction "AS_DATA3,_DATA3_AB7") (pintype "bidirectional"))
    )
    (net (code "27") (name "unconnected-(D4I-nCSO,_DATA4-PadAA7)") (class "Default")
      (node (ref "D4") (pin "AA7") (pinfunction "nCSO,_DATA4_AA7") (pintype "output"))
    )
    (net (code "28") (name "unconnected-(X1-Pad6)") (class "Default")
      (node (ref "X1") (pin "6") (pintype "passive"))
    )
    (net (code "29") (name "unconnected-(X1-Pad7)") (class "Default")
      (node (ref "X1") (pin "7") (pintype "passive"))
    )
    (net (code "30") (name "unconnected-(X1-Pad8)") (class "Default")
      (node (ref "X1") (pin "8") (pintype "passive"))
    )
  )
)
